# 5VBuck_MP2225_P1.net
KiCad netlist of a schematic drawn in EasyEDA Pro
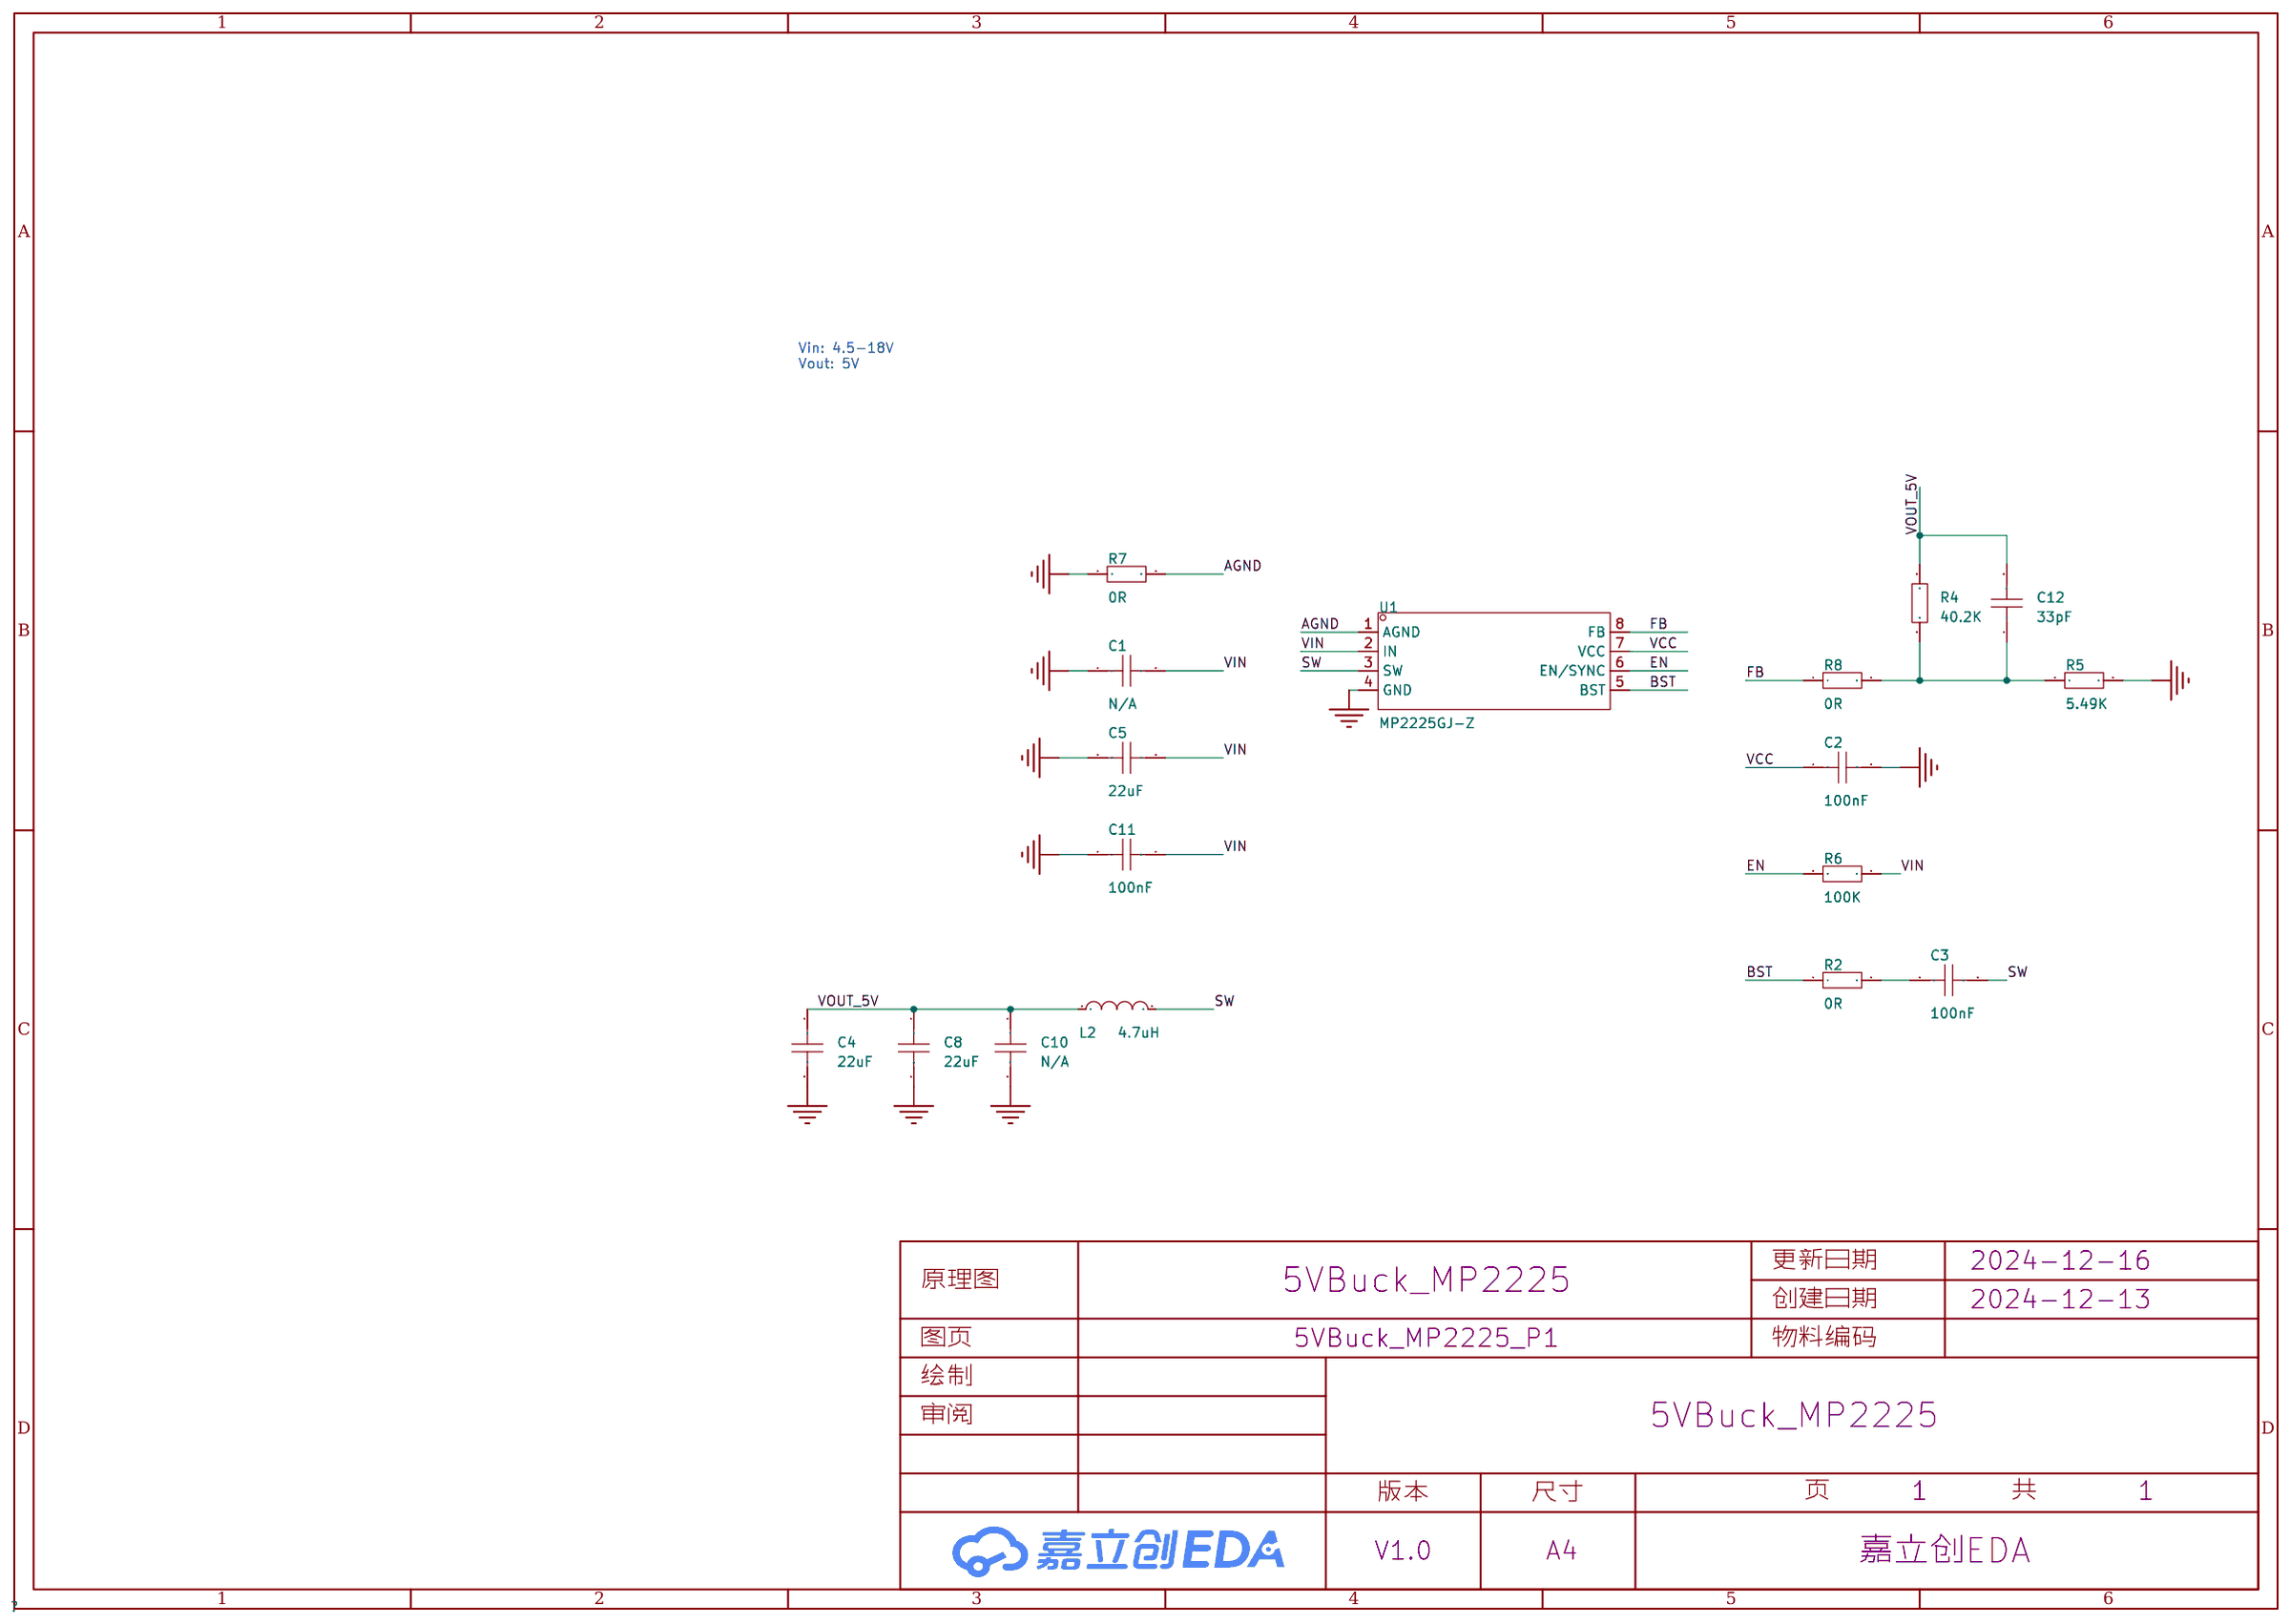
[diagram p0: schematic sheet]

(export (version "E")
  (design (tool "Eeschema 10.0.6"))
  (components
    (comp (ref "C1")
      (value "N/A")
      (footprint "easyedapro:C0805")
      (libsource (lib "easyedapro") (part "CapAcitance"))
    )
    (comp (ref "C2")
      (value "100nF")
      (footprint "easyedapro:C0805")
      (libsource (lib "easyedapro") (part "CapAcitance"))
    )
    (comp (ref "C3")
      (value "100nF")
      (footprint "easyedapro:C0805")
      (libsource (lib "easyedapro") (part "CapAcitance"))
    )
    (comp (ref "C4")
      (value "22uF")
      (footprint "easyedapro:C0805")
      (libsource (lib "easyedapro") (part "CapAcitance"))
    )
    (comp (ref "C5")
      (value "22uF")
      (footprint "easyedapro:C0805")
      (libsource (lib "easyedapro") (part "CapAcitance"))
    )
    (comp (ref "C8")
      (value "22uF")
      (footprint "easyedapro:C0805")
      (libsource (lib "easyedapro") (part "CapAcitance"))
    )
    (comp (ref "C10")
      (value "N/A")
      (footprint "easyedapro:C0805")
      (libsource (lib "easyedapro") (part "CapAcitance"))
    )
    (comp (ref "C11")
      (value "100nF")
      (footprint "easyedapro:C0805")
      (libsource (lib "easyedapro") (part "CapAcitance"))
    )
    (comp (ref "C12")
      (value "33pF")
      (footprint "easyedapro:C0805")
      (libsource (lib "easyedapro") (part "CapAcitance"))
    )
    (comp (ref "L2")
      (value "4.7uH")
      (footprint "easyedapro:IND-SMD_L7.1-W6.6_MJC-0603T")
      (description "电感值:5.6uH;精度:±20%;额定电流:5.5A;饱和电流(Isat):7A;类型:一体成型电感;")
      (fields
        (field (name "Manufacturer Part") "CXP0630-5R6M-AG(5.6uh)")
        (field (name "Manufacturer") "DMBJ(振宝佳)")
      )
      (libsource (lib "easyedapro") (part "CXP0630-5R6M-AG(5.6UH)"))
    )
    (comp (ref "R2") (value "0R") (footprint "easyedapro:R0805") (libsource (lib "easyedapro") (part "电阻")))
    (comp (ref "R4")
      (value "40.2K")
      (footprint "easyedapro:R0805")
      (libsource (lib "easyedapro") (part "电阻"))
    )
    (comp (ref "R5")
      (value "5.49K")
      (footprint "easyedapro:R0805")
      (libsource (lib "easyedapro") (part "电阻"))
    )
    (comp (ref "R6") (value "100K") (footprint "easyedapro:R0805") (libsource (lib "easyedapro") (part "电阻")))
    (comp (ref "R7") (value "0R") (footprint "easyedapro:R0805") (libsource (lib "easyedapro") (part "电阻")))
    (comp (ref "R8") (value "0R") (footprint "easyedapro:R0805") (libsource (lib "easyedapro") (part "电阻")))
    (comp (ref "U1")
      (value "MP2225GJ-Z")
      (footprint "easyedapro:TSOT-23-8_L2.9-W1.6-P0.65-LS2.8-BR")
      (description "功能类型:降压型;输出类型:可调;输入电压:4.5V~18V;输出电压:600mV~18V;输出电流:5A;")
      (fields (field (name "Manufacturer") "MPS(芯源)"))
      (libsource (lib "easyedapro") (part "MP2225GJ-Z"))
    )
  )
  (nets
    (net (code "1") (name "/AGND") (class "Default")
      (node (ref "R7") (pin "2") (pinfunction "2_2") (pintype "input"))
      (node (ref "U1") (pin "1") (pinfunction "AGND_1") (pintype "unspecified"))
    )
    (net (code "2") (name "/BST") (class "Default")
      (node (ref "R2") (pin "1") (pinfunction "1_1") (pintype "input"))
      (node (ref "U1") (pin "5") (pinfunction "BST_5") (pintype "unspecified"))
    )
    (net (code "3") (name "/EN") (class "Default")
      (node (ref "R6") (pin "2") (pinfunction "2_2") (pintype "input"))
      (node (ref "U1") (pin "6") (pinfunction "EN/SYNC_6") (pintype "unspecified"))
    )
    (net (code "4") (name "/FB") (class "Default")
      (node (ref "R8") (pin "1") (pinfunction "1_1") (pintype "input"))
      (node (ref "U1") (pin "8") (pinfunction "FB_8") (pintype "unspecified"))
    )
    (net (code "5") (name "/SW") (class "Default")
      (node (ref "C3") (pin "2") (pinfunction "2_2") (pintype "input"))
      (node (ref "L2") (pin "2") (pinfunction "2_2") (pintype "unspecified"))
      (node (ref "U1") (pin "3") (pinfunction "SW_3") (pintype "unspecified"))
    )
    (net (code "6") (name "/VCC") (class "Default")
      (node (ref "C2") (pin "1") (pinfunction "1_1") (pintype "input"))
      (node (ref "U1") (pin "7") (pinfunction "VCC_7") (pintype "unspecified"))
    )
    (net (code "7") (name "/VIN") (class "Default")
      (node (ref "C1") (pin "2") (pinfunction "2_2") (pintype "input"))
      (node (ref "C11") (pin "2") (pinfunction "2_2") (pintype "input"))
      (node (ref "C5") (pin "2") (pinfunction "2_2") (pintype "input"))
      (node (ref "R6") (pin "1") (pinfunction "1_1") (pintype "input"))
      (node (ref "U1") (pin "2") (pinfunction "IN_2") (pintype "unspecified"))
    )
    (net (code "8") (name "/VOUT_5V") (class "Default")
      (node (ref "C10") (pin "1") (pinfunction "1_1") (pintype "input"))
      (node (ref "C12") (pin "2") (pinfunction "2_2") (pintype "input"))
      (node (ref "C4") (pin "1") (pinfunction "1_1") (pintype "input"))
      (node (ref "C8") (pin "1") (pinfunction "1_1") (pintype "input"))
      (node (ref "L2") (pin "1") (pinfunction "1_1") (pintype "unspecified"))
      (node (ref "R4") (pin "2") (pinfunction "2_2") (pintype "input"))
    )
    (net (code "9") (name "GND") (class "Default")
      (node (ref "C1") (pin "1") (pinfunction "1_1") (pintype "input"))
      (node (ref "C10") (pin "2") (pinfunction "2_2") (pintype "input"))
      (node (ref "C11") (pin "1") (pinfunction "1_1") (pintype "input"))
      (node (ref "C2") (pin "2") (pinfunction "2_2") (pintype "input"))
      (node (ref "C4") (pin "2") (pinfunction "2_2") (pintype "input"))
      (node (ref "C5") (pin "1") (pinfunction "1_1") (pintype "input"))
      (node (ref "C8") (pin "2") (pinfunction "2_2") (pintype "input"))
      (node (ref "R5") (pin "2") (pinfunction "2_2") (pintype "input"))
      (node (ref "R7") (pin "1") (pinfunction "1_1") (pintype "input"))
      (node (ref "U1") (pin "4") (pinfunction "GND_4") (pintype "unspecified"))
    )
    (net (code "10") (name "Net-(C3-Pad1)") (class "Default")
      (node (ref "C3") (pin "1") (pinfunction "1_1") (pintype "input"))
      (node (ref "R2") (pin "2") (pinfunction "2_2") (pintype "input"))
    )
    (net (code "11") (name "Net-(C12-Pad1)") (class "Default")
      (node (ref "C12") (pin "1") (pinfunction "1_1") (pintype "input"))
      (node (ref "R4") (pin "1") (pinfunction "1_1") (pintype "input"))
      (node (ref "R5") (pin "1") (pinfunction "1_1") (pintype "input"))
      (node (ref "R8") (pin "2") (pinfunction "2_2") (pintype "input"))
    )
  )
)
